# Sheet1.net
KiCad netlist of a schematic drawn in Altium Designer
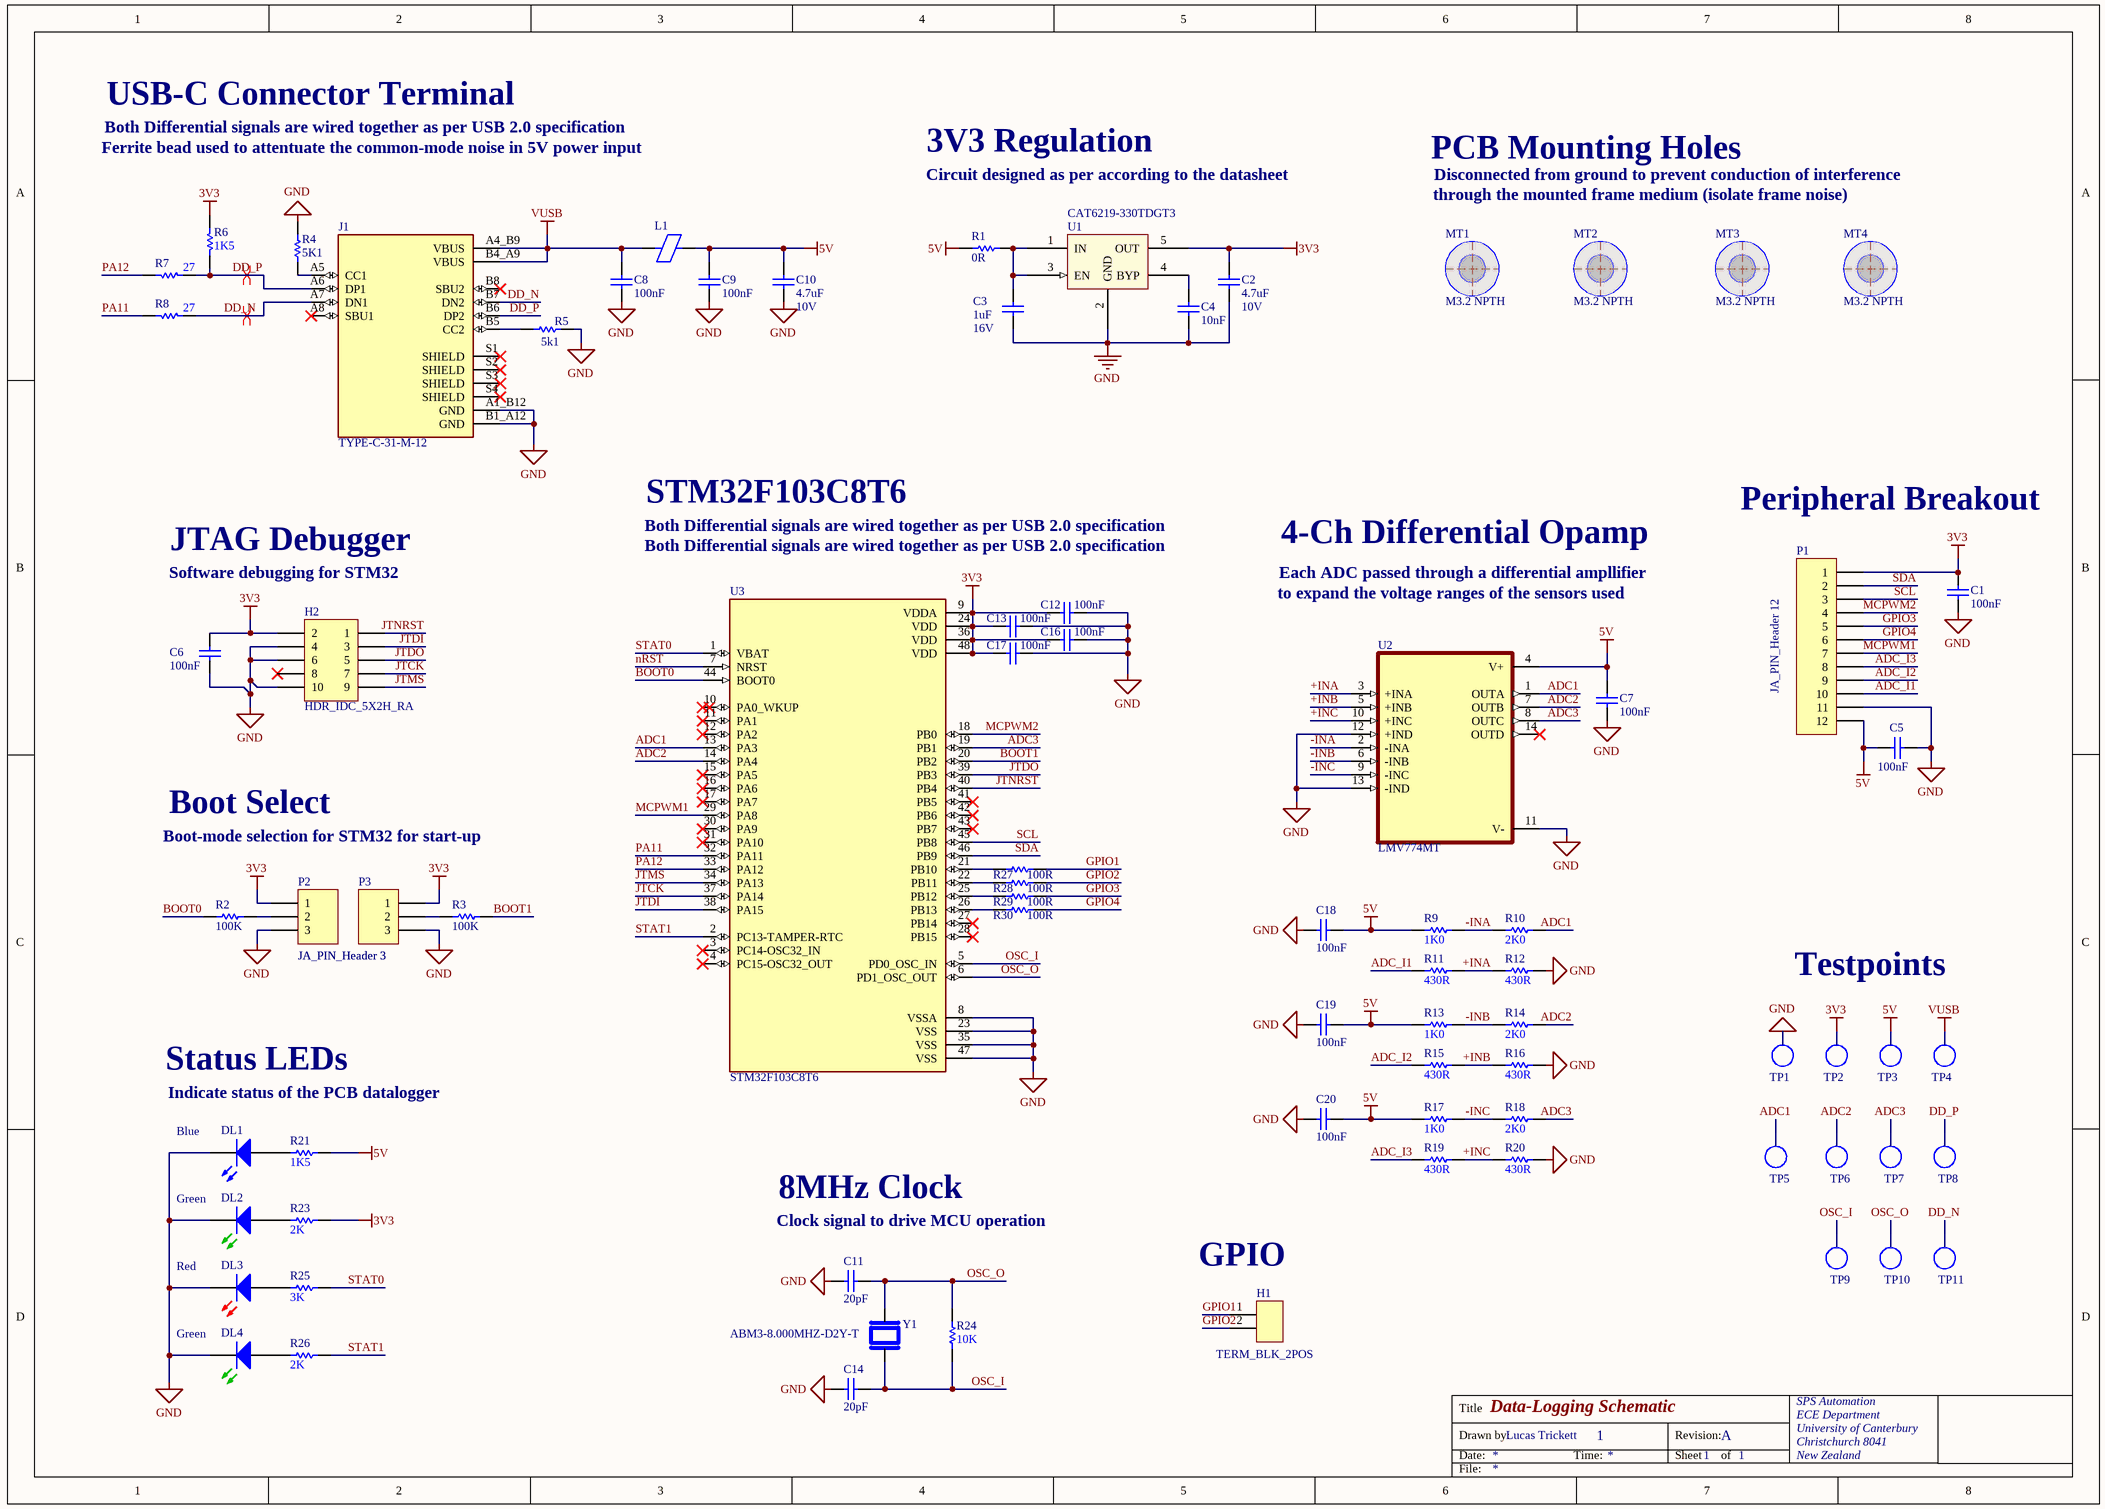
[diagram p0: Sheet1.SchDoc]

(export (version "E")
  (design (tool "Eeschema 10.0.6"))
  (components
    (comp (ref "C1")
      (value "100nF")
      (footprint "CAPC1608L")
      (description "CAP CER 10nF X7R +-10% 50V 0603")
      (libsource (lib "ECE_ComponentsAD23") (part "CC_10nF_0603"))
    )
    (comp (ref "C2")
      (value "4.7uF")
      (footprint "CAPC1608N")
      (description "CAP CER 4.7uF X5R +-20%  10V 0603")
      (fields (field (name "MAX VOLTAGE") "10V"))
      (libsource (lib "ECE_ComponentsAD23") (part "CC_4.7uF_0603"))
    )
    (comp (ref "C3")
      (value "1uF")
      (footprint "CAPC1608L")
      (description "CAP CER 1uF Y5V -20% +80% 16V 0603")
      (fields (field (name "MAX VOLTAGE") "16V"))
      (libsource (lib "ECE_ComponentsAD23") (part "CC_1uF_0603"))
    )
    (comp (ref "C4")
      (value "10nF")
      (footprint "CAPC1608L")
      (description "CAP CER 10nF X7R +-10% 50V 0603")
      (libsource (lib "ECE_ComponentsAD23") (part "CC_10nF_0603"))
    )
    (comp (ref "C5")
      (value "100nF")
      (footprint "CAPC1608L")
      (description "CAP CER 10nF X7R +-10% 50V 0603")
      (libsource (lib "ECE_ComponentsAD23") (part "CC_10nF_0603"))
    )
    (comp (ref "C6")
      (value "100nF")
      (footprint "CAPC1608L")
      (description "CAP CER 10nF X7R +-10% 50V 0603")
      (libsource (lib "ECE_ComponentsAD23") (part "CC_10nF_0603"))
    )
    (comp (ref "C7")
      (value "100nF")
      (footprint "CAPC1608L")
      (description "CAP CER 10nF X7R +-10% 50V 0603")
      (libsource (lib "ECE_ComponentsAD23") (part "CC_10nF_0603"))
    )
    (comp (ref "C8")
      (value "100nF")
      (footprint "CAPC1608L")
      (description "CAP CER 10nF X7R +-10% 50V 0603")
      (libsource (lib "ECE_ComponentsAD23") (part "CC_10nF_0603"))
    )
    (comp (ref "C9")
      (value "100nF")
      (footprint "CAPC1608L")
      (description "CAP CER 10nF X7R +-10% 50V 0603")
      (libsource (lib "ECE_ComponentsAD23") (part "CC_10nF_0603"))
    )
    (comp (ref "C10")
      (value "4.7uF")
      (footprint "CAPC1608N")
      (description "CAP CER 4.7uF X5R +-20%  10V 0603")
      (fields (field (name "MAX VOLTAGE") "10V"))
      (libsource (lib "ECE_ComponentsAD23") (part "CC_4.7uF_0603"))
    )
    (comp (ref "C11")
      (value "20pF")
      (footprint "CAPC1608L")
      (description "CAP CER 27pF NPO/COG +-5% 50V 0603")
      (fields (field (name "Comment") "10pF"))
      (libsource (lib "ECE_ComponentsAD23") (part "CC_27pF_0603"))
    )
    (comp (ref "C12")
      (value "100nF")
      (footprint "CAPC1608L")
      (description "CAP CER 10nF X7R +-10% 50V 0603")
      (libsource (lib "ECE_ComponentsAD23") (part "CC_10nF_0603"))
    )
    (comp (ref "C13")
      (value "100nF")
      (footprint "CAPC1608L")
      (description "CAP CER 10nF X7R +-10% 50V 0603")
      (libsource (lib "ECE_ComponentsAD23") (part "CC_10nF_0603"))
    )
    (comp (ref "C14")
      (value "20pF")
      (footprint "CAPC1608L")
      (description "CAP CER 27pF NPO/COG +-5% 50V 0603")
      (fields (field (name "Comment") "10pF"))
      (libsource (lib "ECE_ComponentsAD23") (part "CC_27pF_0603"))
    )
    (comp (ref "C16")
      (value "100nF")
      (footprint "CAPC1608L")
      (description "CAP CER 10nF X7R +-10% 50V 0603")
      (libsource (lib "ECE_ComponentsAD23") (part "CC_10nF_0603"))
    )
    (comp (ref "C17")
      (value "100nF")
      (footprint "CAPC1608L")
      (description "CAP CER 10nF X7R +-10% 50V 0603")
      (libsource (lib "ECE_ComponentsAD23") (part "CC_10nF_0603"))
    )
    (comp (ref "C18")
      (value "100nF")
      (footprint "CAPC1608L")
      (description "CAP CER 10nF X7R +-10% 50V 0603")
      (libsource (lib "ECE_ComponentsAD23") (part "CC_10nF_0603"))
    )
    (comp (ref "C19")
      (value "100nF")
      (footprint "CAPC1608L")
      (description "CAP CER 10nF X7R +-10% 50V 0603")
      (libsource (lib "ECE_ComponentsAD23") (part "CC_10nF_0603"))
    )
    (comp (ref "C20")
      (value "100nF")
      (footprint "CAPC1608L")
      (description "CAP CER 10nF X7R +-10% 50V 0603")
      (libsource (lib "ECE_ComponentsAD23") (part "CC_10nF_0603"))
    )
    (comp (ref "DL1")
      (value "Blue")
      (footprint "WL-SMCW0603")
      (description "LED Blue 270mcd 0603 SMD")
      (fields
        (field (name "MANUFACTURER") "WURTH ELEKTRONIK")
        (field (name "MANUFACTURER PART NUMBER") "150060BS75000")
        (field (name "LED COLOUR") "Blue")
      )
      (libsource (lib "ECE_ComponentsAD23") (part "DL_150060BS75000"))
    )
    (comp (ref "DL2")
      (value "Green")
      (footprint "WL-SMCW0603")
      (description "LED Green 430mcd 0603 SMD")
      (fields
        (field (name "MANUFACTURER") "WURTH ELEKTRONIK")
        (field (name "MANUFACTURER PART NUMBER") "150060GS75000")
        (field (name "LED COLOUR") "Green")
      )
      (libsource (lib "ECE_ComponentsAD23") (part "DL_150060GS75000"))
    )
    (comp (ref "DL3")
      (value "Red")
      (footprint "WL-SMCW0603")
      (description "LED Red 250mcd 0603 SMD")
      (fields
        (field (name "MANUFACTURER") "WURTH ELEKTRONIK")
        (field (name "MANUFACTURER PART NUMBER") "150060RS75000")
        (field (name "LED COLOUR") "Red")
      )
      (libsource (lib "ECE_ComponentsAD23") (part "DL_150060RS75000"))
    )
    (comp (ref "DL4")
      (value "Green")
      (footprint "WL-SMCW0603")
      (description "LED Green 430mcd 0603 SMD")
      (fields
        (field (name "MANUFACTURER") "WURTH ELEKTRONIK")
        (field (name "MANUFACTURER PART NUMBER") "150060GS75000")
        (field (name "LED COLOUR") "Green")
      )
      (libsource (lib "ECE_ComponentsAD23") (part "DL_150060GS75000"))
    )
    (comp (ref "H1")
      (value "TERM_BLK_2POS")
      (footprint "TERM_BLK_2POS")
      (description "2 Position Terminal Block 7.62mm spacing")
      (libsource (lib "ENCE461AD23") (part "TERM_BLK_2POS"))
    )
    (comp (ref "H2")
      (value "HDR_IDC_5X2H_RA")
      (footprint "IDC2.54-H10C")
      (description "IDC Header, 2.54mm, 10-Pin, Right Angle")
      (libsource (lib "ECE_ComponentsAD23") (part "JA_HDR_IDC_5X2_R/A"))
    )
    (comp (ref "J1")
      (value "TYPE-C-31-M-12")
      (footprint "HRO_TYPE-C-31-M-12")
      (description "USB Connectors 24 Receptacle 1 8.94*7.3mm RoHS")
      (fields (field (name "MF") "HRO Electronics Co., Ltd."))
      (libsource (lib "Lucas Trickett") (part "TYPE-C-31-M-12"))
    )
    (comp (ref "L1")
      (value "1A max, Idc 0.3R,")
      (footprint "INDC3216L")
      (description "Ferrite Bead, Rdc 0.3R, Z100MHZ 600R, Imax 1A, SMD 1206")
      (fields
        (field (name "MANUFACTURER") "FAIR-RITE")
        (field (name "MANUFACTURER PART NUMBER") "2512066017Y1")
      )
      (libsource (lib "ECE_ComponentsAD23") (part "IN_Ferrite-Bead"))
    )
    (comp (ref "MT1")
      (value "M3.2 NPTH")
      (footprint "MNT-HOLE_3.2mm_NPTH")
      (description "Fixing M3.2 Mount Hole NPTH")
      (fields (field (name "MANUFACTURER") "Hi-Q"))
      (libsource (lib "ECE_ComponentsAD23") (part "MC_M3.2_HOLE"))
    )
    (comp (ref "MT2")
      (value "M3.2 NPTH")
      (footprint "MNT-HOLE_3.2mm_NPTH")
      (description "Fixing M3.2 Mount Hole NPTH")
      (fields (field (name "MANUFACTURER") "Hi-Q"))
      (libsource (lib "ECE_ComponentsAD23") (part "MC_M3.2_HOLE"))
    )
    (comp (ref "MT3")
      (value "M3.2 NPTH")
      (footprint "MNT-HOLE_3.2mm_NPTH")
      (description "Fixing M3.2 Mount Hole NPTH")
      (fields (field (name "MANUFACTURER") "Hi-Q"))
      (libsource (lib "ECE_ComponentsAD23") (part "MC_M3.2_HOLE"))
    )
    (comp (ref "MT4")
      (value "M3.2 NPTH")
      (footprint "MNT-HOLE_3.2mm_NPTH")
      (description "Fixing M3.2 Mount Hole NPTH")
      (fields (field (name "MANUFACTURER") "Hi-Q"))
      (libsource (lib "ECE_ComponentsAD23") (part "MC_M3.2_HOLE"))
    )
    (comp (ref "P1")
      (value "JA_PIN_Header 12")
      (footprint "HDR1X12")
      (description "Header, 12-Pin")
      (fields (field (name "PUBLISHER") "Altium Limited"))
      (libsource (lib "ECE_ComponentsAD23") (part "JA_PIN_Header 12"))
    )
    (comp (ref "P2")
      (value "JA_PIN_Header 3")
      (footprint "HDR1X3")
      (description "Header, 3-Pin")
      (fields (field (name "PUBLISHER") "Altium Limited"))
      (libsource (lib "") (part "JA_PIN_Header 3_1"))
    )
    (comp (ref "P3")
      (value "JA_PIN_Header 3")
      (footprint "HDR1X3")
      (description "Header, 3-Pin")
      (fields (field (name "PUBLISHER") "Altium Limited"))
      (libsource (lib "ECE_ComponentsAD23") (part "JA_PIN_Header 3"))
    )
    (comp (ref "R1")
      (value "0R")
      (footprint "RESC1608L")
      (description "RES 0.0 OHM 1/10W 5% 0603 SMD")
      (libsource (lib "ECE_ComponentsAD23") (part "RS_0R0"))
    )
    (comp (ref "R2")
      (value "100K")
      (footprint "RESC1608L")
      (description "RES 100K OHM 1/10W 5% 0603 SMD")
      (libsource (lib "ECE_ComponentsAD23") (part "RS_100K"))
    )
    (comp (ref "R3")
      (value "100K")
      (footprint "RESC1608L")
      (description "RES 100K OHM 1/10W 5% 0603 SMD")
      (libsource (lib "ECE_ComponentsAD23") (part "RS_100K"))
    )
    (comp (ref "R4")
      (value "5K1")
      (footprint "RESC1608L")
      (description "RES 100K OHM 1/10W 5% 0603 SMD")
      (libsource (lib "ECE_ComponentsAD23") (part "RS_100K"))
    )
    (comp (ref "R5")
      (value "5k1")
      (footprint "RESC1608L")
      (description "RES 100K OHM 1/10W 5% 0603 SMD")
      (libsource (lib "ECE_ComponentsAD23") (part "RS_100K"))
    )
    (comp (ref "R6")
      (value "1K5")
      (footprint "RESC1608L")
      (description "RES 2K OHM 1/10W 5% 0603 SMD")
      (libsource (lib "ECE_ComponentsAD23") (part "RS_2K"))
    )
    (comp (ref "R7")
      (value "27")
      (footprint "RESC1608L")
      (description "RES 2K OHM 1/10W 5% 0603 SMD")
      (libsource (lib "ECE_ComponentsAD23") (part "RS_2K"))
    )
    (comp (ref "R8")
      (value "27")
      (footprint "RESC1608L")
      (description "RES 2K OHM 1/10W 5% 0603 SMD")
      (libsource (lib "ECE_ComponentsAD23") (part "RS_2K"))
    )
    (comp (ref "R9")
      (value "1K0")
      (footprint "RESC1608L")
      (description "RES 430 OHM 1/10W 5% 0603 SMD")
      (libsource (lib "ECE_ComponentsAD23") (part "RS_430R"))
    )
    (comp (ref "R10")
      (value "2K0")
      (footprint "RESC1608L")
      (description "RES 430 OHM 1/10W 5% 0603 SMD")
      (libsource (lib "ECE_ComponentsAD23") (part "RS_430R"))
    )
    (comp (ref "R11")
      (value "430R")
      (footprint "RESC1608L")
      (description "RES 430 OHM 1/10W 5% 0603 SMD")
      (libsource (lib "ECE_ComponentsAD23") (part "RS_430R"))
    )
    (comp (ref "R12")
      (value "430R")
      (footprint "RESC1608L")
      (description "RES 430 OHM 1/10W 5% 0603 SMD")
      (libsource (lib "ECE_ComponentsAD23") (part "RS_430R"))
    )
    (comp (ref "R13")
      (value "1K0")
      (footprint "RESC1608L")
      (description "RES 430 OHM 1/10W 5% 0603 SMD")
      (libsource (lib "ECE_ComponentsAD23") (part "RS_430R"))
    )
    (comp (ref "R14")
      (value "2K0")
      (footprint "RESC1608L")
      (description "RES 430 OHM 1/10W 5% 0603 SMD")
      (libsource (lib "ECE_ComponentsAD23") (part "RS_430R"))
    )
    (comp (ref "R15")
      (value "430R")
      (footprint "RESC1608L")
      (description "RES 430 OHM 1/10W 5% 0603 SMD")
      (libsource (lib "ECE_ComponentsAD23") (part "RS_430R"))
    )
    (comp (ref "R16")
      (value "430R")
      (footprint "RESC1608L")
      (description "RES 430 OHM 1/10W 5% 0603 SMD")
      (libsource (lib "ECE_ComponentsAD23") (part "RS_430R"))
    )
    (comp (ref "R17")
      (value "1K0")
      (footprint "RESC1608L")
      (description "RES 430 OHM 1/10W 5% 0603 SMD")
      (libsource (lib "ECE_ComponentsAD23") (part "RS_430R"))
    )
    (comp (ref "R18")
      (value "2K0")
      (footprint "RESC1608L")
      (description "RES 430 OHM 1/10W 5% 0603 SMD")
      (libsource (lib "ECE_ComponentsAD23") (part "RS_430R"))
    )
    (comp (ref "R19")
      (value "430R")
      (footprint "RESC1608L")
      (description "RES 430 OHM 1/10W 5% 0603 SMD")
      (libsource (lib "ECE_ComponentsAD23") (part "RS_430R"))
    )
    (comp (ref "R20")
      (value "430R")
      (footprint "RESC1608L")
      (description "RES 430 OHM 1/10W 5% 0603 SMD")
      (libsource (lib "ECE_ComponentsAD23") (part "RS_430R"))
    )
    (comp (ref "R21")
      (value "1K5")
      (footprint "RESC1608L")
      (description "RES 2K OHM 1/10W 5% 0603 SMD")
      (libsource (lib "ECE_ComponentsAD23") (part "RS_2K"))
    )
    (comp (ref "R23")
      (value "2K")
      (footprint "RESC1608L")
      (description "RES 2K OHM 1/10W 5% 0603 SMD")
      (libsource (lib "ECE_ComponentsAD23") (part "RS_2K"))
    )
    (comp (ref "R24")
      (value "10K")
      (footprint "RESC1608L")
      (description "RES 2K OHM 1/10W 5% 0603 SMD")
      (libsource (lib "ECE_ComponentsAD23") (part "RS_2K"))
    )
    (comp (ref "R25")
      (value "3K")
      (footprint "RESC1608L")
      (description "RES 3K OHM 1/10W 5% 0603 SMD")
      (libsource (lib "ECE_ComponentsAD23") (part "RS_3K"))
    )
    (comp (ref "R26")
      (value "2K")
      (footprint "RESC1608L")
      (description "RES 2K OHM 1/10W 5% 0603 SMD")
      (libsource (lib "ECE_ComponentsAD23") (part "RS_2K"))
    )
    (comp (ref "R27")
      (value "100R")
      (footprint "RESC1608L")
      (description "RES 100 OHM 1/10W 5% 0603 SMD")
      (libsource (lib "ECE_ComponentsAD23") (part "RS_100R"))
    )
    (comp (ref "R28")
      (value "100R")
      (footprint "RESC1608L")
      (description "RES 100 OHM 1/10W 5% 0603 SMD")
      (libsource (lib "ECE_ComponentsAD23") (part "RS_100R"))
    )
    (comp (ref "R29")
      (value "100R")
      (footprint "RESC1608L")
      (description "RES 100 OHM 1/10W 5% 0603 SMD")
      (libsource (lib "ECE_ComponentsAD23") (part "RS_100R"))
    )
    (comp (ref "R30")
      (value "100R")
      (footprint "RESC1608L")
      (description "RES 100 OHM 1/10W 5% 0603 SMD")
      (libsource (lib "ECE_ComponentsAD23") (part "RS_100R"))
    )
    (comp (ref "TP1")
      (value "TP_0603")
      (footprint "TP_0603")
      (description "Test Point 1.65X0.9X1.2mm SMD")
      (fields
        (field (name "MANUFACTURER") "TE Connectivity AMP Connectors")
        (field (name "MANUFACTURER PART NUMBER") "1625854-3")
      )
      (libsource (lib "ECE_ComponentsAD23") (part "TP_0603"))
    )
    (comp (ref "TP2")
      (value "TP_0603")
      (footprint "TP_0603")
      (description "Test Point 1.65X0.9X1.2mm SMD")
      (fields
        (field (name "MANUFACTURER") "TE Connectivity AMP Connectors")
        (field (name "MANUFACTURER PART NUMBER") "1625854-3")
      )
      (libsource (lib "ECE_ComponentsAD23") (part "TP_0603"))
    )
    (comp (ref "TP3")
      (value "TP_0603")
      (footprint "TP_0603")
      (description "Test Point 1.65X0.9X1.2mm SMD")
      (fields
        (field (name "MANUFACTURER") "TE Connectivity AMP Connectors")
        (field (name "MANUFACTURER PART NUMBER") "1625854-3")
      )
      (libsource (lib "ECE_ComponentsAD23") (part "TP_0603"))
    )
    (comp (ref "TP4")
      (value "TP_0603")
      (footprint "TP_0603")
      (description "Test Point 1.65X0.9X1.2mm SMD")
      (fields
        (field (name "MANUFACTURER") "TE Connectivity AMP Connectors")
        (field (name "MANUFACTURER PART NUMBER") "1625854-3")
      )
      (libsource (lib "ECE_ComponentsAD23") (part "TP_0603"))
    )
    (comp (ref "TP5")
      (value "TP_0603")
      (footprint "TP_0603")
      (description "Test Point 1.65X0.9X1.2mm SMD")
      (fields
        (field (name "MANUFACTURER") "TE Connectivity AMP Connectors")
        (field (name "MANUFACTURER PART NUMBER") "1625854-3")
      )
      (libsource (lib "ECE_ComponentsAD23") (part "TP_0603"))
    )
    (comp (ref "TP6")
      (value "TP_0603")
      (footprint "TP_0603")
      (description "Test Point 1.65X0.9X1.2mm SMD")
      (fields
        (field (name "MANUFACTURER") "TE Connectivity AMP Connectors")
        (field (name "MANUFACTURER PART NUMBER") "1625854-3")
      )
      (libsource (lib "ECE_ComponentsAD23") (part "TP_0603"))
    )
    (comp (ref "TP7")
      (value "TP_0603")
      (footprint "TP_0603")
      (description "Test Point 1.65X0.9X1.2mm SMD")
      (fields
        (field (name "MANUFACTURER") "TE Connectivity AMP Connectors")
        (field (name "MANUFACTURER PART NUMBER") "1625854-3")
      )
      (libsource (lib "ECE_ComponentsAD23") (part "TP_0603"))
    )
    (comp (ref "TP8")
      (value "TP_0603")
      (footprint "TP_0603")
      (description "Test Point 1.65X0.9X1.2mm SMD")
      (fields
        (field (name "MANUFACTURER") "TE Connectivity AMP Connectors")
        (field (name "MANUFACTURER PART NUMBER") "1625854-3")
      )
      (libsource (lib "ECE_ComponentsAD23") (part "TP_0603"))
    )
    (comp (ref "TP9")
      (value "TP_0603")
      (footprint "TP_0603")
      (description "Test Point 1.65X0.9X1.2mm SMD")
      (fields
        (field (name "MANUFACTURER") "TE Connectivity AMP Connectors")
        (field (name "MANUFACTURER PART NUMBER") "1625854-3")
      )
      (libsource (lib "ECE_ComponentsAD23") (part "TP_0603"))
    )
    (comp (ref "TP10")
      (value "TP_0603")
      (footprint "TP_0603")
      (description "Test Point 1.65X0.9X1.2mm SMD")
      (fields
        (field (name "MANUFACTURER") "TE Connectivity AMP Connectors")
        (field (name "MANUFACTURER PART NUMBER") "1625854-3")
      )
      (libsource (lib "ECE_ComponentsAD23") (part "TP_0603"))
    )
    (comp (ref "TP11")
      (value "TP_0603")
      (footprint "TP_0603")
      (description "Test Point 1.65X0.9X1.2mm SMD")
      (fields
        (field (name "MANUFACTURER") "TE Connectivity AMP Connectors")
        (field (name "MANUFACTURER PART NUMBER") "1625854-3")
      )
      (libsource (lib "ECE_ComponentsAD23") (part "TP_0603"))
    )
    (comp (ref "U1")
      (value "CAT6219-330TDGT3")
      (footprint "SOT95P280X145-5N")
      (description "IC REG LIN 3.3V 500MA TSOT23-5")
      (fields
        (field (name "BASE PART NUMBER") "CAT6219")
        (field (name "SUPPLIER PART NUMBER") "CAT6219-330TDGT3")
      )
      (libsource (lib "ENCE461AD23") (part "SV_CAT6219-330TDGT3"))
    )
    (comp (ref "U2")
      (value "LMV774MT")
      (footprint "SOP65P640X120-14N")
      (description "Quad, Low Offset, Low Noise, RRO Operational Amplifiers")
      (fields
        (field (name "MP") "LMV774MTX/NOPB")
        (field (name "DIGI-KEY_PART_NUMBER") "LMV774MTX/NOPBTR-ND")
      )
      (libsource (lib "Lucas Trickett") (part "LMV774MT"))
    )
    (comp (ref "U3")
      (value "STM32F103C8T6")
      (footprint "QFP50P900X900X160-48N")
      (description "ARM® Cortex®-M3 STM32F1 Microcontroller IC 32-Bit 72MHz 64KB (64K x 8) FLASH 48-LQFP (7x7)")
      (fields (field (name "MF") "STMicroelectronics"))
      (libsource (lib "Lucas Trickett") (part "STM32F103C8T6"))
    )
    (comp (ref "Y1")
      (value "ABM3-8.000MHZ-D2Y-T")
      (footprint "XTAL_ABM3-8.000MHZ-D2Y-T")
      (description "8 MHz Â±20ppm Crystal 18pF 140 Ohms 2-SMD, No Lead")
      (fields (field (name "MF") "Abracon"))
      (libsource (lib "Lucas Trickett") (part "ABM3-8.000MHZ-D2Y-T"))
    )
  )
  (nets
    (net (code "1") (name "/+INA") (class "Default")
      (node (ref "R11") (pin "2") (pinfunction "2_2") (pintype "passive"))
      (node (ref "R12") (pin "2") (pinfunction "2_2") (pintype "passive"))
      (node (ref "U2") (pin "3") (pinfunction "+INA_3") (pintype "input"))
    )
    (net (code "2") (name "/+INB") (class "Default")
      (node (ref "R15") (pin "2") (pinfunction "2_2") (pintype "passive"))
      (node (ref "R16") (pin "2") (pinfunction "2_2") (pintype "passive"))
      (node (ref "U2") (pin "5") (pinfunction "+INB_5") (pintype "input"))
    )
    (net (code "3") (name "/+INC") (class "Default")
      (node (ref "R19") (pin "2") (pinfunction "2_2") (pintype "passive"))
      (node (ref "R20") (pin "2") (pinfunction "2_2") (pintype "passive"))
      (node (ref "U2") (pin "10") (pinfunction "+INC_10") (pintype "input"))
    )
    (net (code "4") (name "/-INA") (class "Default")
      (node (ref "R10") (pin "1") (pinfunction "1_1") (pintype "passive"))
      (node (ref "R9") (pin "2") (pinfunction "2_2") (pintype "passive"))
      (node (ref "U2") (pin "2") (pinfunction "-INA_2") (pintype "input"))
    )
    (net (code "5") (name "/-INB") (class "Default")
      (node (ref "R13") (pin "2") (pinfunction "2_2") (pintype "passive"))
      (node (ref "R14") (pin "1") (pinfunction "1_1") (pintype "passive"))
      (node (ref "U2") (pin "6") (pinfunction "-INB_6") (pintype "input"))
    )
    (net (code "6") (name "/-INC") (class "Default")
      (node (ref "R17") (pin "2") (pinfunction "2_2") (pintype "passive"))
      (node (ref "R18") (pin "1") (pinfunction "1_1") (pintype "passive"))
      (node (ref "U2") (pin "9") (pinfunction "-INC_9") (pintype "input"))
    )
    (net (code "7") (name "/ADC1") (class "Default")
      (node (ref "R10") (pin "2") (pinfunction "2_2") (pintype "passive"))
      (node (ref "TP5") (pin "1") (pinfunction "TP_1") (pintype "passive"))
      (node (ref "U2") (pin "1") (pinfunction "OUTA_1") (pintype "output"))
      (node (ref "U3") (pin "13") (pinfunction "PA3_13") (pintype "bidirectional"))
    )
    (net (code "8") (name "/ADC2") (class "Default")
      (node (ref "R14") (pin "2") (pinfunction "2_2") (pintype "passive"))
      (node (ref "TP6") (pin "1") (pinfunction "TP_1") (pintype "passive"))
      (node (ref "U2") (pin "7") (pinfunction "OUTB_7") (pintype "output"))
      (node (ref "U3") (pin "14") (pinfunction "PA4_14") (pintype "bidirectional"))
    )
    (net (code "9") (name "/ADC3") (class "Default")
      (node (ref "R18") (pin "2") (pinfunction "2_2") (pintype "passive"))
      (node (ref "TP7") (pin "1") (pinfunction "TP_1") (pintype "passive"))
      (node (ref "U2") (pin "8") (pinfunction "OUTC_8") (pintype "output"))
      (node (ref "U3") (pin "19") (pinfunction "PB1_19") (pintype "bidirectional"))
    )
    (net (code "10") (name "/ADC_I1") (class "Default")
      (node (ref "P1") (pin "10") (pinfunction "10_10") (pintype "passive"))
      (node (ref "R11") (pin "1") (pinfunction "1_1") (pintype "passive"))
    )
    (net (code "11") (name "/ADC_I2") (class "Default")
      (node (ref "P1") (pin "9") (pinfunction "9_9") (pintype "passive"))
      (node (ref "R15") (pin "1") (pinfunction "1_1") (pintype "passive"))
    )
    (net (code "12") (name "/ADC_I3") (class "Default")
      (node (ref "P1") (pin "8") (pinfunction "8_8") (pintype "passive"))
      (node (ref "R19") (pin "1") (pinfunction "1_1") (pintype "passive"))
    )
    (net (code "13") (name "/BOOT0") (class "Default")
      (node (ref "R2") (pin "1") (pinfunction "1_1") (pintype "passive"))
      (node (ref "U3") (pin "44") (pinfunction "BOOT0_44") (pintype "input"))
    )
    (net (code "14") (name "/BOOT1") (class "Default")
      (node (ref "R3") (pin "2") (pinfunction "2_2") (pintype "passive"))
      (node (ref "U3") (pin "20") (pinfunction "PB2_20") (pintype "bidirectional"))
    )
    (net (code "15") (name "/DD_N") (class "Default")
      (node (ref "J1") (pin "A7") (pinfunction "DN1_A7") (pintype "bidirectional"))
      (node (ref "J1") (pin "B7") (pinfunction "DN2_B7") (pintype "bidirectional"))
      (node (ref "R8") (pin "2") (pinfunction "2_2") (pintype "passive"))
      (node (ref "TP11") (pin "1") (pinfunction "TP_1") (pintype "passive"))
    )
    (net (code "16") (name "/DD_P") (class "Default")
      (node (ref "J1") (pin "A6") (pinfunction "DP1_A6") (pintype "bidirectional"))
      (node (ref "J1") (pin "B6") (pinfunction "DP2_B6") (pintype "bidirectional"))
      (node (ref "R6") (pin "2") (pinfunction "2_2") (pintype "passive"))
      (node (ref "R7") (pin "2") (pinfunction "2_2") (pintype "passive"))
      (node (ref "TP8") (pin "1") (pinfunction "TP_1") (pintype "passive"))
    )
    (net (code "17") (name "/GPIO1") (class "Default")
      (node (ref "H1") (pin "1") (pintype "passive"))
      (node (ref "R27") (pin "2") (pinfunction "2_2") (pintype "passive"))
    )
    (net (code "18") (name "/GPIO2") (class "Default")
      (node (ref "H1") (pin "2") (pintype "passive"))
      (node (ref "R28") (pin "2") (pinfunction "2_2") (pintype "passive"))
    )
    (net (code "19") (name "/GPIO3") (class "Default")
      (node (ref "P1") (pin "5") (pinfunction "5_5") (pintype "passive"))
      (node (ref "R29") (pin "2") (pinfunction "2_2") (pintype "passive"))
    )
    (net (code "20") (name "/GPIO4") (class "Default")
      (node (ref "P1") (pin "6") (pinfunction "6_6") (pintype "passive"))
      (node (ref "R30") (pin "2") (pinfunction "2_2") (pintype "passive"))
    )
    (net (code "21") (name "/JTCK") (class "Default")
      (node (ref "H2") (pin "7") (pinfunction "7_7") (pintype "passive"))
      (node (ref "U3") (pin "37") (pinfunction "PA14_37") (pintype "bidirectional"))
    )
    (net (code "22") (name "/JTDI") (class "Default")
      (node (ref "H2") (pin "3") (pinfunction "3_3") (pintype "passive"))
      (node (ref "U3") (pin "38") (pinfunction "PA15_38") (pintype "bidirectional"))
    )
    (net (code "23") (name "/JTDO") (class "Default")
      (node (ref "H2") (pin "5") (pinfunction "5_5") (pintype "passive"))
      (node (ref "U3") (pin "39") (pinfunction "PB3_39") (pintype "bidirectional"))
    )
    (net (code "24") (name "/JTMS") (class "Default")
      (node (ref "H2") (pin "9") (pinfunction "9_9") (pintype "passive"))
      (node (ref "U3") (pin "34") (pinfunction "PA13_34") (pintype "bidirectional"))
    )
    (net (code "25") (name "/JTNRST") (class "Default")
      (node (ref "H2") (pin "1") (pinfunction "1_1") (pintype "passive"))
      (node (ref "U3") (pin "40") (pinfunction "PB4_40") (pintype "bidirectional"))
    )
    (net (code "26") (name "/MCPWM1") (class "Default")
      (node (ref "P1") (pin "7") (pinfunction "7_7") (pintype "passive"))
      (node (ref "U3") (pin "29") (pinfunction "PA8_29") (pintype "bidirectional"))
    )
    (net (code "27") (name "/MCPWM2") (class "Default")
      (node (ref "P1") (pin "4") (pinfunction "4_4") (pintype "passive"))
      (node (ref "U3") (pin "18") (pinfunction "PB0_18") (pintype "bidirectional"))
    )
    (net (code "28") (name "/OSC_I") (class "Default")
      (node (ref "C14") (pin "2") (pinfunction "2_2") (pintype "passive"))
      (node (ref "R24") (pin "1") (pinfunction "1_1") (pintype "passive"))
      (node (ref "TP9") (pin "1") (pinfunction "TP_1") (pintype "passive"))
      (node (ref "U3") (pin "5") (pinfunction "PD0_OSC_IN_5") (pintype "bidirectional"))
      (node (ref "Y1") (pin "1") (pinfunction "1_1") (pintype "passive"))
    )
    (net (code "29") (name "/OSC_O") (class "Default")
      (node (ref "C11") (pin "2") (pinfunction "2_2") (pintype "passive"))
      (node (ref "R24") (pin "2") (pinfunction "2_2") (pintype "passive"))
      (node (ref "TP10") (pin "1") (pinfunction "TP_1") (pintype "passive"))
      (node (ref "U3") (pin "6") (pinfunction "PD1_OSC_OUT_6") (pintype "bidirectional"))
      (node (ref "Y1") (pin "2") (pinfunction "2_2") (pintype "passive"))
    )
    (net (code "30") (name "/PA11") (class "Default")
      (node (ref "R8") (pin "1") (pinfunction "1_1") (pintype "passive"))
      (node (ref "U3") (pin "32") (pinfunction "PA11_32") (pintype "bidirectional"))
    )
    (net (code "31") (name "/PA12") (class "Default")
      (node (ref "R7") (pin "1") (pinfunction "1_1") (pintype "passive"))
      (node (ref "U3") (pin "33") (pinfunction "PA12_33") (pintype "bidirectional"))
    )
    (net (code "32") (name "/SCL") (class "Default")
      (node (ref "P1") (pin "3") (pinfunction "3_3") (pintype "passive"))
      (node (ref "U3") (pin "45") (pinfunction "PB8_45") (pintype "bidirectional"))
    )
    (net (code "33") (name "/SDA") (class "Default")
      (node (ref "P1") (pin "2") (pinfunction "2_2") (pintype "passive"))
      (node (ref "U3") (pin "46") (pinfunction "PB9_46") (pintype "bidirectional"))
    )
    (net (code "34") (name "/STAT0") (class "Default")
      (node (ref "R25") (pin "2") (pinfunction "2_2") (pintype "passive"))
      (node (ref "U3") (pin "1") (pinfunction "VBAT_1") (pintype "bidirectional"))
    )
    (net (code "35") (name "/STAT1") (class "Default")
      (node (ref "R26") (pin "2") (pinfunction "2_2") (pintype "passive"))
      (node (ref "U3") (pin "2") (pinfunction "PC13-TAMPER-RTC_2") (pintype "bidirectional"))
    )
    (net (code "36") (name "/nRST") (class "Default")
      (node (ref "U3") (pin "7") (pinfunction "NRST_7") (pintype "input"))
    )
    (net (code "37") (name "3V3") (class "Default")
      (node (ref "C1") (pin "1") (pinfunction "1_1") (pintype "passive"))
      (node (ref "C12") (pin "2") (pinfunction "2_2") (pintype "passive"))
      (node (ref "C13") (pin "2") (pinfunction "2_2") (pintype "passive"))
      (node (ref "C16") (pin "2") (pinfunction "2_2") (pintype "passive"))
      (node (ref "C17") (pin "2") (pinfunction "2_2") (pintype "passive"))
      (node (ref "C2") (pin "1") (pinfunction "1_1") (pintype "passive"))
      (node (ref "C6") (pin "2") (pinfunction "2_2") (pintype "passive"))
      (node (ref "H2") (pin "2") (pinfunction "2_2") (pintype "passive"))
      (node (ref "P1") (pin "1") (pinfunction "1_1") (pintype "passive"))
      (node (ref "P2") (pin "1") (pinfunction "1_1") (pintype "passive"))
      (node (ref "P3") (pin "1") (pinfunction "1_1") (pintype "passive"))
      (node (ref "R23") (pin "2") (pinfunction "2_2") (pintype "passive"))
      (node (ref "R6") (pin "1") (pinfunction "1_1") (pintype "passive"))
      (node (ref "TP2") (pin "1") (pinfunction "TP_1") (pintype "passive"))
      (node (ref "U1") (pin "5") (pinfunction "OUT_5") (pintype "power_in"))
      (node (ref "U3") (pin "24") (pinfunction "VDD_24") (pintype "power_in"))
      (node (ref "U3") (pin "36") (pinfunction "VDD_36") (pintype "power_in"))
      (node (ref "U3") (pin "48") (pinfunction "VDD_48") (pintype "power_in"))
      (node (ref "U3") (pin "9") (pinfunction "VDDA_9") (pintype "power_in"))
    )
    (net (code "38") (name "5V") (class "Default")
      (node (ref "C10") (pin "2") (pinfunction "2_2") (pintype "passive"))
      (node (ref "C18") (pin "2") (pinfunction "2_2") (pintype "passive"))
      (node (ref "C19") (pin "2") (pinfunction "2_2") (pintype "passive"))
      (node (ref "C20") (pin "2") (pinfunction "2_2") (pintype "passive"))
      (node (ref "C5") (pin "2") (pinfunction "2_2") (pintype "passive"))
      (node (ref "C7") (pin "2") (pinfunction "2_2") (pintype "passive"))
      (node (ref "C9") (pin "1") (pinfunction "1_1") (pintype "passive"))
      (node (ref "L1") (pin "2") (pinfunction "2_2") (pintype "passive"))
      (node (ref "P1") (pin "12") (pinfunction "12_12") (pintype "passive"))
      (node (ref "R1") (pin "2") (pinfunction "2_2") (pintype "passive"))
      (node (ref "R13") (pin "1") (pinfunction "1_1") (pintype "passive"))
      (node (ref "R17") (pin "1") (pinfunction "1_1") (pintype "passive"))
      (node (ref "R21") (pin "2") (pinfunction "2_2") (pintype "passive"))
      (node (ref "R9") (pin "1") (pinfunction "1_1") (pintype "passive"))
      (node (ref "TP3") (pin "1") (pinfunction "TP_1") (pintype "passive"))
      (node (ref "U2") (pin "4") (pinfunction "V+_4") (pintype "power_in"))
    )
    (net (code "39") (name "GND") (class "Default")
      (node (ref "C1") (pin "2") (pinfunction "2_2") (pintype "passive"))
      (node (ref "C10") (pin "1") (pinfunction "1_1") (pintype "passive"))
      (node (ref "C11") (pin "1") (pinfunction "1_1") (pintype "passive"))
      (node (ref "C12") (pin "1") (pinfunction "1_1") (pintype "passive"))
      (node (ref "C13") (pin "1") (pinfunction "1_1") (pintype "passive"))
      (node (ref "C14") (pin "1") (pinfunction "1_1") (pintype "passive"))
      (node (ref "C16") (pin "1") (pinfunction "1_1") (pintype "passive"))
      (node (ref "C17") (pin "1") (pinfunction "1_1") (pintype "passive"))
      (node (ref "C18") (pin "1") (pinfunction "1_1") (pintype "passive"))
      (node (ref "C19") (pin "1") (pinfunction "1_1") (pintype "passive"))
      (node (ref "C2") (pin "2") (pinfunction "2_2") (pintype "passive"))
      (node (ref "C20") (pin "1") (pinfunction "1_1") (pintype "passive"))
      (node (ref "C3") (pin "2") (pinfunction "2_2") (pintype "passive"))
      (node (ref "C4") (pin "2") (pinfunction "2_2") (pintype "passive"))
      (node (ref "C5") (pin "1") (pinfunction "1_1") (pintype "passive"))
      (node (ref "C6") (pin "1") (pinfunction "1_1") (pintype "passive"))
      (node (ref "C7") (pin "1") (pinfunction "1_1") (pintype "passive"))
      (node (ref "C8") (pin "2") (pinfunction "2_2") (pintype "passive"))
      (node (ref "C9") (pin "2") (pinfunction "2_2") (pintype "passive"))
      (node (ref "DL1") (pin "1") (pinfunction "K_1") (pintype "passive"))
      (node (ref "DL2") (pin "1") (pinfunction "K_1") (pintype "passive"))
      (node (ref "DL3") (pin "1") (pinfunction "K_1") (pintype "passive"))
      (node (ref "DL4") (pin "1") (pinfunction "K_1") (pintype "passive"))
      (node (ref "H2") (pin "10") (pinfunction "10_10") (pintype "passive"))
      (node (ref "H2") (pin "4") (pinfunction "4_4") (pintype "passive"))
      (node (ref "H2") (pin "6") (pinfunction "6_6") (pintype "passive"))
      (node (ref "J1") (pin "A1_B12") (pinfunction "GND_A1_B12") (pintype "power_in"))
      (node (ref "J1") (pin "B1_A12") (pinfunction "GND_B1_A12") (pintype "power_in"))
      (node (ref "P1") (pin "11") (pinfunction "11_11") (pintype "passive"))
      (node (ref "P2") (pin "3") (pinfunction "3_3") (pintype "passive"))
      (node (ref "P3") (pin "3") (pinfunction "3_3") (pintype "passive"))
      (node (ref "R12") (pin "1") (pinfunction "1_1") (pintype "passive"))
      (node (ref "R16") (pin "1") (pinfunction "1_1") (pintype "passive"))
      (node (ref "R20") (pin "1") (pinfunction "1_1") (pintype "passive"))
      (node (ref "R4") (pin "2") (pinfunction "2_2") (pintype "passive"))
      (node (ref "R5") (pin "2") (pinfunction "2_2") (pintype "passive"))
      (node (ref "TP1") (pin "1") (pinfunction "TP_1") (pintype "passive"))
      (node (ref "U1") (pin "2") (pinfunction "GND_2") (pintype "power_in"))
      (node (ref "U2") (pin "11") (pinfunction "V-_11") (pintype "power_in"))
      (node (ref "U2") (pin "12") (pinfunction "+IND_12") (pintype "input"))
      (node (ref "U2") (pin "13") (pinfunction "-IND_13") (pintype "input"))
      (node (ref "U3") (pin "23") (pinfunction "VSS_23") (pintype "power_in"))
      (node (ref "U3") (pin "35") (pinfunction "VSS_35") (pintype "power_in"))
      (node (ref "U3") (pin "47") (pinfunction "VSS_47") (pintype "power_in"))
      (node (ref "U3") (pin "8") (pinfunction "VSSA_8") (pintype "power_in"))
    )
    (net (code "40") (name "Net-(DL1-A)") (class "Default")
      (node (ref "DL1") (pin "2") (pinfunction "A_2") (pintype "passive"))
      (node (ref "R21") (pin "1") (pinfunction "1_1") (pintype "passive"))
    )
    (net (code "41") (name "Net-(DL2-A)") (class "Default")
      (node (ref "DL2") (pin "2") (pinfunction "A_2") (pintype "passive"))
      (node (ref "R23") (pin "1") (pinfunction "1_1") (pintype "passive"))
    )
    (net (code "42") (name "Net-(DL3-A)") (class "Default")
      (node (ref "DL3") (pin "2") (pinfunction "A_2") (pintype "passive"))
      (node (ref "R25") (pin "1") (pinfunction "1_1") (pintype "passive"))
    )
    (net (code "43") (name "Net-(DL4-A)") (class "Default")
      (node (ref "DL4") (pin "2") (pinfunction "A_2") (pintype "passive"))
      (node (ref "R26") (pin "1") (pinfunction "1_1") (pintype "passive"))
    )
    (net (code "44") (name "Net-(J1-CC1)") (class "Default")
      (node (ref "J1") (pin "A5") (pinfunction "CC1_A5") (pintype "bidirectional"))
      (node (ref "R4") (pin "1") (pinfunction "1_1") (pintype "passive"))
    )
    (net (code "45") (name "Net-(J1-CC2)") (class "Default")
      (node (ref "J1") (pin "B5") (pinfunction "CC2_B5") (pintype "bidirectional"))
      (node (ref "R5") (pin "1") (pinfunction "1_1") (pintype "passive"))
    )
    (net (code "46") (name "Net-(P2-Pad2)") (class "Default")
      (node (ref "P2") (pin "2") (pinfunction "2_2") (pintype "passive"))
      (node (ref "R2") (pin "2") (pinfunction "2_2") (pintype "passive"))
    )
    (net (code "47") (name "Net-(P3-Pad2)") (class "Default")
      (node (ref "P3") (pin "2") (pinfunction "2_2") (pintype "passive"))
      (node (ref "R3") (pin "1") (pinfunction "1_1") (pintype "passive"))
    )
    (net (code "48") (name "Net-(U1-BYP)") (class "Default")
      (node (ref "C4") (pin "1") (pinfunction "1_1") (pintype "passive"))
      (node (ref "U1") (pin "4") (pinfunction "BYP_4") (pintype "passive"))
    )
    (net (code "49") (name "Net-(U1-EN)") (class "Default")
      (node (ref "C3") (pin "1") (pinfunction "1_1") (pintype "passive"))
      (node (ref "R1") (pin "1") (pinfunction "1_1") (pintype "passive"))
      (node (ref "U1") (pin "1") (pinfunction "IN_1") (pintype "power_in"))
      (node (ref "U1") (pin "3") (pinfunction "EN_3") (pintype "input"))
    )
    (net (code "50") (name "Net-(U3-PB10)") (class "Default")
      (node (ref "R27") (pin "1") (pinfunction "1_1") (pintype "passive"))
      (node (ref "U3") (pin "21") (pinfunction "PB10_21") (pintype "bidirectional"))
    )
    (net (code "51") (name "Net-(U3-PB11)") (class "Default")
      (node (ref "R28") (pin "1") (pinfunction "1_1") (pintype "passive"))
      (node (ref "U3") (pin "22") (pinfunction "PB11_22") (pintype "bidirectional"))
    )
    (net (code "52") (name "Net-(U3-PB12)") (class "Default")
      (node (ref "R29") (pin "1") (pinfunction "1_1") (pintype "passive"))
      (node (ref "U3") (pin "25") (pinfunction "PB12_25") (pintype "bidirectional"))
    )
    (net (code "53") (name "Net-(U3-PB13)") (class "Default")
      (node (ref "R30") (pin "1") (pinfunction "1_1") (pintype "passive"))
      (node (ref "U3") (pin "26") (pinfunction "PB13_26") (pintype "bidirectional"))
    )
    (net (code "54") (name "VUSB") (class "Default")
      (node (ref "C8") (pin "1") (pinfunction "1_1") (pintype "passive"))
      (node (ref "J1") (pin "A4_B9") (pinfunction "VBUS_A4_B9") (pintype "power_in"))
      (node (ref "J1") (pin "B4_A9") (pinfunction "VBUS_B4_A9") (pintype "power_in"))
      (node (ref "L1") (pin "1") (pinfunction "1_1") (pintype "passive"))
      (node (ref "TP4") (pin "1") (pinfunction "TP_1") (pintype "passive"))
    )
    (net (code "55") (name "unconnected-(H2-Pad8)") (class "Default")
      (node (ref "H2") (pin "8") (pinfunction "8_8") (pintype "passive+no_connect"))
    )
    (net (code "56") (name "unconnected-(J1-SBU1-PadA8)") (class "Default")
      (node (ref "J1") (pin "A8") (pinfunction "SBU1_A8") (pintype "bidirectional+no_connect"))
    )
    (net (code "57") (name "unconnected-(J1-SBU2-PadB8)") (class "Default")
      (node (ref "J1") (pin "B8") (pinfunction "SBU2_B8") (pintype "bidirectional+no_connect"))
    )
    (net (code "58") (name "unconnected-(J1-SHIELD-PadS1)") (class "Default")
      (node (ref "J1") (pin "S1") (pinfunction "SHIELD_S1") (pintype "passive+no_connect"))
    )
    (net (code "59") (name "unconnected-(J1-SHIELD-PadS2)") (class "Default")
      (node (ref "J1") (pin "S2") (pinfunction "SHIELD_S2") (pintype "passive+no_connect"))
    )
    (net (code "60") (name "unconnected-(J1-SHIELD-PadS3)") (class "Default")
      (node (ref "J1") (pin "S3") (pinfunction "SHIELD_S3") (pintype "passive+no_connect"))
    )
    (net (code "61") (name "unconnected-(J1-SHIELD-PadS4)") (class "Default")
      (node (ref "J1") (pin "S4") (pinfunction "SHIELD_S4") (pintype "passive+no_connect"))
    )
    (net (code "62") (name "unconnected-(U2-OUTD-Pad14)") (class "Default")
      (node (ref "U2") (pin "14") (pinfunction "OUTD_14") (pintype "output+no_connect"))
    )
    (net (code "63") (name "unconnected-(U3-PA0_WKUP-Pad10)") (class "Default")
      (node (ref "U3") (pin "10") (pinfunction "PA0_WKUP_10") (pintype "bidirectional+no_connect"))
    )
    (net (code "64") (name "unconnected-(U3-PA1-Pad11)") (class "Default")
      (node (ref "U3") (pin "11") (pinfunction "PA1_11") (pintype "bidirectional+no_connect"))
    )
    (net (code "65") (name "unconnected-(U3-PA2-Pad12)") (class "Default")
      (node (ref "U3") (pin "12") (pinfunction "PA2_12") (pintype "bidirectional+no_connect"))
    )
    (net (code "66") (name "unconnected-(U3-PA5-Pad15)") (class "Default")
      (node (ref "U3") (pin "15") (pinfunction "PA5_15") (pintype "bidirectional+no_connect"))
    )
    (net (code "67") (name "unconnected-(U3-PA6-Pad16)") (class "Default")
      (node (ref "U3") (pin "16") (pinfunction "PA6_16") (pintype "bidirectional+no_connect"))
    )
    (net (code "68") (name "unconnected-(U3-PA7-Pad17)") (class "Default")
      (node (ref "U3") (pin "17") (pinfunction "PA7_17") (pintype "bidirectional+no_connect"))
    )
    (net (code "69") (name "unconnected-(U3-PA9-Pad30)") (class "Default")
      (node (ref "U3") (pin "30") (pinfunction "PA9_30") (pintype "bidirectional+no_connect"))
    )
    (net (code "70") (name "unconnected-(U3-PA10-Pad31)") (class "Default")
      (node (ref "U3") (pin "31") (pinfunction "PA10_31") (pintype "bidirectional+no_connect"))
    )
    (net (code "71") (name "unconnected-(U3-PB5-Pad41)") (class "Default")
      (node (ref "U3") (pin "41") (pinfunction "PB5_41") (pintype "bidirectional+no_connect"))
    )
    (net (code "72") (name "unconnected-(U3-PB6-Pad42)") (class "Default")
      (node (ref "U3") (pin "42") (pinfunction "PB6_42") (pintype "bidirectional+no_connect"))
    )
    (net (code "73") (name "unconnected-(U3-PB7-Pad43)") (class "Default")
      (node (ref "U3") (pin "43") (pinfunction "PB7_43") (pintype "bidirectional+no_connect"))
    )
    (net (code "74") (name "unconnected-(U3-PB14-Pad27)") (class "Default")
      (node (ref "U3") (pin "27") (pinfunction "PB14_27") (pintype "bidirectional+no_connect"))
    )
    (net (code "75") (name "unconnected-(U3-PB15-Pad28)") (class "Default")
      (node (ref "U3") (pin "28") (pinfunction "PB15_28") (pintype "bidirectional+no_connect"))
    )
    (net (code "76") (name "unconnected-(U3-PC14-OSC32_IN-Pad3)") (class "Default")
      (node (ref "U3") (pin "3") (pinfunction "PC14-OSC32_IN_3") (pintype "bidirectional+no_connect"))
    )
    (net (code "77") (name "unconnected-(U3-PC15-OSC32_OUT-Pad4)") (class "Default")
      (node (ref "U3") (pin "4") (pinfunction "PC15-OSC32_OUT_4") (pintype "bidirectional+no_connect"))
    )
  )
)
